# LTC3114.net
KiCad netlist of a schematic drawn in EAGLE
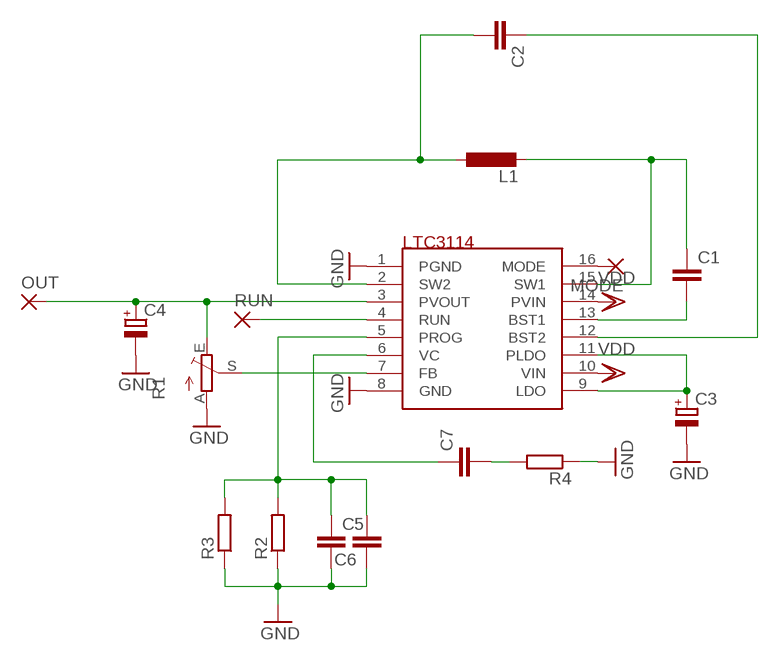
[diagram p0: schematic, sheet 1]

(export (version "E")
  (design (tool "Eeschema 10.0.6"))
  (components
    (comp (ref "C1")
      (value "C-EUC0805")
      (footprint "eagle-import:C0805")
      (libsource (lib "eagle-import") (part "resistor_C-EUC0805"))
    )
    (comp (ref "C2")
      (value "C-EUC0805")
      (footprint "eagle-import:C0805")
      (libsource (lib "eagle-import") (part "resistor_C-EUC0805"))
    )
    (comp (ref "C3")
      (value "CPOL-EUE2,5-6E")
      (footprint "eagle-import:E2,5-6E")
      (libsource (lib "eagle-import") (part "CPOL-EUE2,5-6E"))
    )
    (comp (ref "C4")
      (value "CPOL-EUE2,5-6E")
      (footprint "eagle-import:E2,5-6E")
      (libsource (lib "eagle-import") (part "CPOL-EUE2,5-6E"))
    )
    (comp (ref "C5")
      (value "C-EUC0805")
      (footprint "eagle-import:C0805")
      (libsource (lib "eagle-import") (part "C-EUC0805"))
    )
    (comp (ref "C6")
      (value "C-EU025-025X050")
      (footprint "eagle-import:C025-025X050")
      (libsource (lib "eagle-import") (part "resistor_C-EU025-025X050"))
    )
    (comp (ref "C7")
      (value "C-EUC0805")
      (footprint "eagle-import:C0805")
      (libsource (lib "eagle-import") (part "C-EUC0805"))
    )
    (comp (ref "L1")
      (value "L-EUL3225M")
      (footprint "eagle-import:L3225M")
      (libsource (lib "eagle-import") (part "L-EUL3225M"))
    )
    (comp (ref "MODE")
      (value "1,6/0,8")
      (footprint "eagle-import:1,6_0,8")
      (libsource (lib "eagle-import") (part "1,6/0,8"))
    )
    (comp (ref "OUT")
      (value "1,6/0,8")
      (footprint "eagle-import:1,6_0,8")
      (libsource (lib "eagle-import") (part "1,6/0,8"))
    )
    (comp (ref "R1")
      (value "TRIM_EU-RJ9W")
      (footprint "eagle-import:RJ9W")
      (libsource (lib "eagle-import") (part "TRIM_EU-RJ9W"))
    )
    (comp (ref "R2")
      (value "R-EU_M0805")
      (footprint "eagle-import:M0805")
      (libsource (lib "eagle-import") (part "R-EU_M0805"))
    )
    (comp (ref "R3")
      (value "R-EU_0204/7")
      (footprint "eagle-import:0204_7")
      (libsource (lib "eagle-import") (part "R-EU_0204/7"))
    )
    (comp (ref "R4")
      (value "R-EU_M0805")
      (footprint "eagle-import:M0805")
      (libsource (lib "eagle-import") (part "R-EU_M0805"))
    )
    (comp (ref "RUN")
      (value "1,6/0,8")
      (footprint "eagle-import:1,6_0,8")
      (libsource (lib "eagle-import") (part "1,6/0,8"))
    )
    (comp (ref "U$1")
      (value "LTC3114")
      (footprint "eagle-import:TSSOP16")
      (libsource (lib "eagle-import") (part "LTC3114"))
    )
  )
  (nets
    (net (code "1") (name "GND") (class "Default")
      (node (ref "C3") (pin "-") (pinfunction "-_-") (pintype "passive"))
      (node (ref "C4") (pin "-") (pinfunction "-_-") (pintype "passive"))
      (node (ref "C5") (pin "2") (pinfunction "2_2") (pintype "passive"))
      (node (ref "C6") (pin "1") (pinfunction "1_1") (pintype "passive"))
      (node (ref "R1") (pin "A") (pinfunction "A_A") (pintype "passive"))
      (node (ref "R2") (pin "1") (pinfunction "1_1") (pintype "passive"))
      (node (ref "R3") (pin "1") (pinfunction "1_1") (pintype "passive"))
      (node (ref "R4") (pin "1") (pinfunction "1_1") (pintype "passive"))
      (node (ref "U$1") (pin "1") (pinfunction "PGND_1") (pintype "bidirectional"))
      (node (ref "U$1") (pin "8") (pinfunction "GND_8") (pintype "bidirectional"))
    )
    (net (code "2") (name "Net-(C7-Pad2)") (class "Default")
      (node (ref "C7") (pin "2") (pinfunction "2_2") (pintype "passive"))
      (node (ref "R4") (pin "2") (pinfunction "2_2") (pintype "passive"))
    )
    (net (code "3") (name "Net-(MODE-P)") (class "Default")
      (node (ref "MODE") (pin "1") (pinfunction "P_1") (pintype "passive"))
      (node (ref "U$1") (pin "16") (pinfunction "MODE_16") (pintype "bidirectional"))
    )
    (net (code "4") (name "Net-(OUT-P)") (class "Default")
      (node (ref "C4") (pin "+") (pinfunction "+_+") (pintype "passive"))
      (node (ref "OUT") (pin "1") (pinfunction "P_1") (pintype "passive"))
      (node (ref "R1") (pin "E") (pinfunction "E_E") (pintype "passive"))
      (node (ref "U$1") (pin "3") (pinfunction "PVOUT_3") (pintype "bidirectional"))
    )
    (net (code "5") (name "Net-(RUN-P)") (class "Default")
      (node (ref "RUN") (pin "1") (pinfunction "P_1") (pintype "passive"))
      (node (ref "U$1") (pin "4") (pinfunction "RUN_4") (pintype "bidirectional"))
    )
    (net (code "6") (name "Net-(U$1-BST1)") (class "Default")
      (node (ref "C1") (pin "2") (pinfunction "2_2") (pintype "passive"))
      (node (ref "U$1") (pin "13") (pinfunction "BST1_13") (pintype "bidirectional"))
    )
    (net (code "7") (name "Net-(U$1-BST2)") (class "Default")
      (node (ref "C2") (pin "1") (pinfunction "1_1") (pintype "passive"))
      (node (ref "U$1") (pin "12") (pinfunction "BST2_12") (pintype "bidirectional"))
    )
    (net (code "8") (name "Net-(U$1-FB)") (class "Default")
      (node (ref "R1") (pin "S") (pinfunction "S_S") (pintype "passive"))
      (node (ref "U$1") (pin "7") (pinfunction "FB_7") (pintype "bidirectional"))
    )
    (net (code "9") (name "Net-(U$1-LDO)") (class "Default")
      (node (ref "C3") (pin "+") (pinfunction "+_+") (pintype "passive"))
      (node (ref "U$1") (pin "11") (pinfunction "PLDO_11") (pintype "bidirectional"))
      (node (ref "U$1") (pin "9") (pinfunction "LDO_9") (pintype "bidirectional"))
    )
    (net (code "10") (name "Net-(U$1-PROG)") (class "Default")
      (node (ref "C5") (pin "1") (pinfunction "1_1") (pintype "passive"))
      (node (ref "C6") (pin "2") (pinfunction "2_2") (pintype "passive"))
      (node (ref "R2") (pin "2") (pinfunction "2_2") (pintype "passive"))
      (node (ref "R3") (pin "2") (pinfunction "2_2") (pintype "passive"))
      (node (ref "U$1") (pin "5") (pinfunction "PROG_5") (pintype "bidirectional"))
    )
    (net (code "11") (name "Net-(U$1-SW1)") (class "Default")
      (node (ref "C1") (pin "1") (pinfunction "1_1") (pintype "passive"))
      (node (ref "L1") (pin "2") (pinfunction "2_2") (pintype "passive"))
      (node (ref "U$1") (pin "15") (pinfunction "SW1_15") (pintype "bidirectional"))
    )
    (net (code "12") (name "Net-(U$1-SW2)") (class "Default")
      (node (ref "C2") (pin "2") (pinfunction "2_2") (pintype "passive"))
      (node (ref "L1") (pin "1") (pinfunction "1_1") (pintype "passive"))
      (node (ref "U$1") (pin "2") (pinfunction "SW2_2") (pintype "bidirectional"))
    )
    (net (code "13") (name "Net-(U$1-VC)") (class "Default")
      (node (ref "C7") (pin "1") (pinfunction "1_1") (pintype "passive"))
      (node (ref "U$1") (pin "6") (pinfunction "VC_6") (pintype "bidirectional"))
    )
    (net (code "14") (name "VDD") (class "Default")
      (node (ref "U$1") (pin "10") (pinfunction "VIN_10") (pintype "bidirectional"))
      (node (ref "U$1") (pin "14") (pinfunction "PVIN_14") (pintype "bidirectional"))
    )
  )
)
